# ProPrj_Simagic_qr_wheelside_adapter_pass.net
KiCad netlist of a schematic drawn in EasyEDA Pro
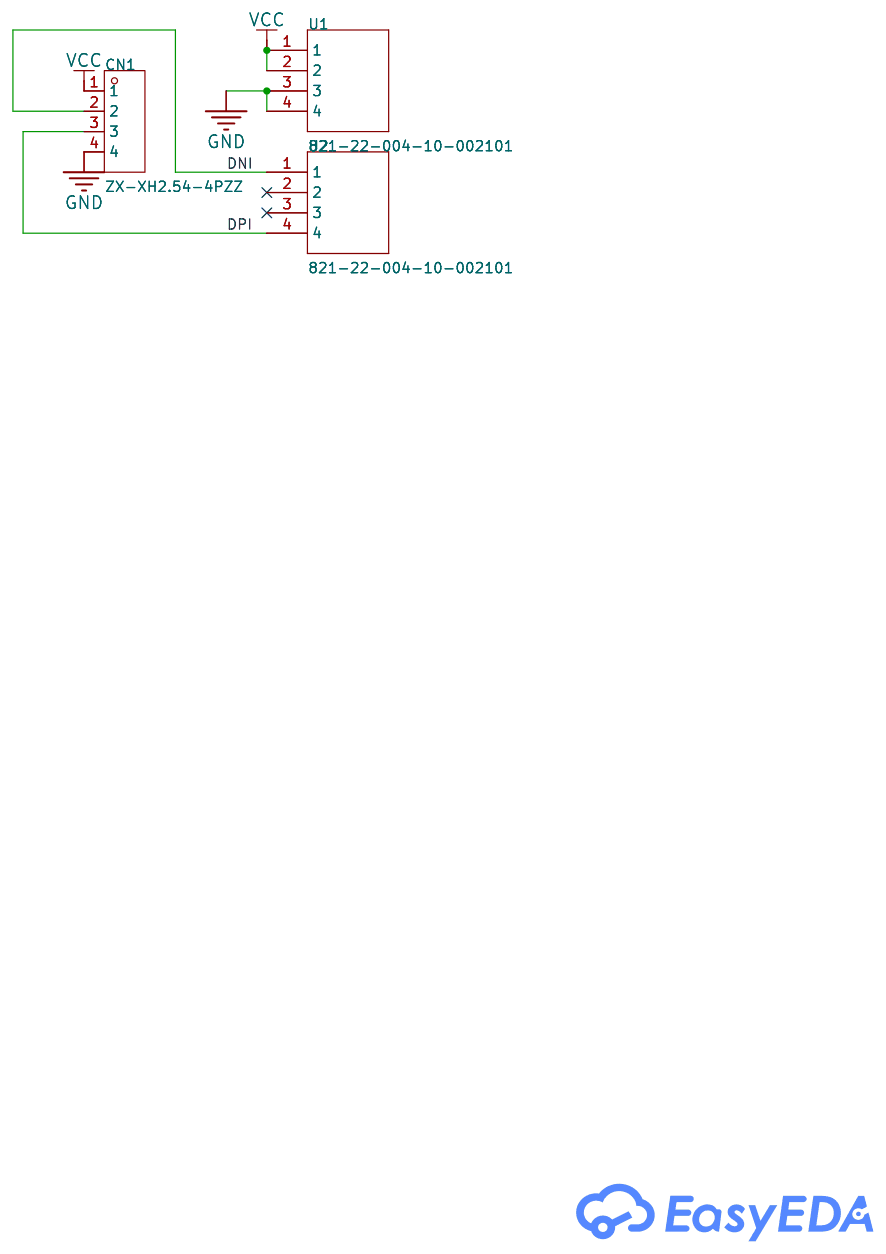
[diagram p0: schematic sheet]

(export (version "E")
  (design (tool "Eeschema 10.0.6"))
  (components
    (comp (ref "CN1")
      (value "ZX-XH2.54-4PZZ")
      (footprint "easyedapro:CONN-TH_4P-P2.50_4PIN")
      (fields (field (name "Manufacturer") "Megastar(兆星)"))
      (libsource (lib "easyedapro") (part "ZX-XH2.54-4PZZ"))
    )
    (comp (ref "U1")
      (value "821-22-004-10-002101")
      (footprint "easyedapro:HDRV4W43P0X254_1X4_1016X254X50")
      (libsource (lib "easyedapro") (part "821-22-004-10-002101"))
    )
    (comp (ref "U2")
      (value "821-22-004-10-002101")
      (footprint "easyedapro:HDRV4W43P0X254_1X4_1016X254X50")
      (libsource (lib "easyedapro") (part "821-22-004-10-002101"))
    )
  )
  (nets
    (net (code "1") (name "/DNI") (class "Default")
      (node (ref "CN1") (pin "2") (pinfunction "2_2") (pintype "unspecified"))
      (node (ref "U2") (pin "1") (pinfunction "1_1") (pintype "bidirectional"))
    )
    (net (code "2") (name "/DPI") (class "Default")
      (node (ref "CN1") (pin "3") (pinfunction "3_3") (pintype "unspecified"))
      (node (ref "U2") (pin "4") (pinfunction "4_4") (pintype "bidirectional"))
    )
    (net (code "3") (name "GND") (class "Default")
      (node (ref "CN1") (pin "4") (pinfunction "4_4") (pintype "unspecified"))
      (node (ref "U1") (pin "3") (pinfunction "3_3") (pintype "bidirectional"))
      (node (ref "U1") (pin "4") (pinfunction "4_4") (pintype "bidirectional"))
    )
    (net (code "4") (name "VCC") (class "Default")
      (node (ref "CN1") (pin "1") (pinfunction "1_1") (pintype "unspecified"))
      (node (ref "U1") (pin "1") (pinfunction "1_1") (pintype "bidirectional"))
      (node (ref "U1") (pin "2") (pinfunction "2_2") (pintype "bidirectional"))
    )
    (net (code "5") (name "unconnected-(U2-Pad2)") (class "Default")
      (node (ref "U2") (pin "2") (pinfunction "2_2") (pintype "bidirectional+no_connect"))
    )
    (net (code "6") (name "unconnected-(U2-Pad3)") (class "Default")
      (node (ref "U2") (pin "3") (pinfunction "3_3") (pintype "bidirectional+no_connect"))
    )
  )
)
